# bln-002.net
KiCad netlist of a schematic drawn in EAGLE
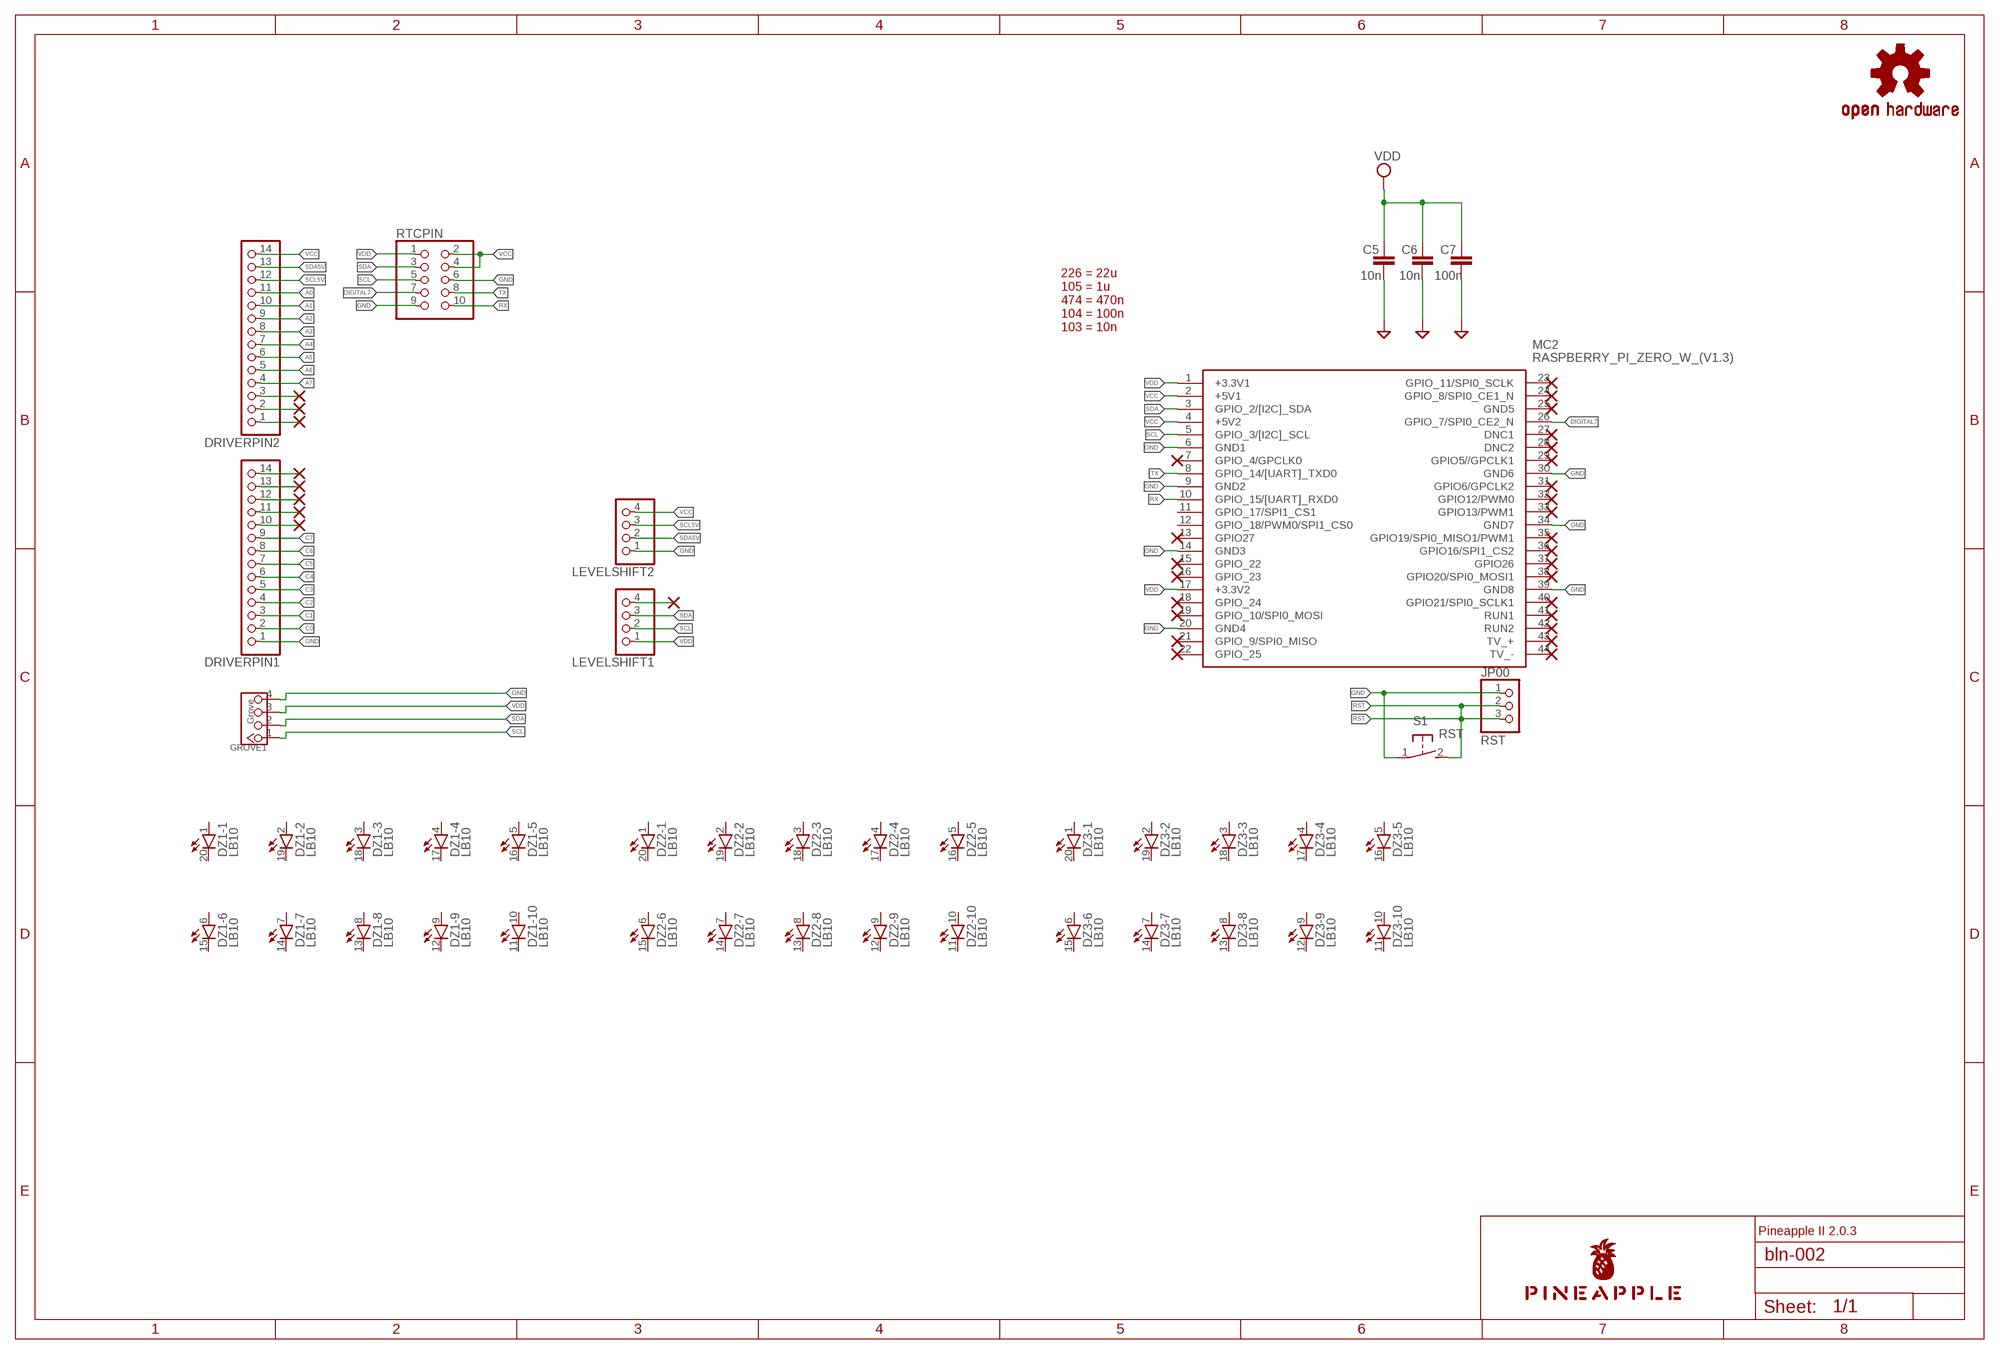
[diagram p0: schematic, sheet 1]

(export (version "E")
  (design (tool "Eeschema 10.0.6"))
  (components
    (comp (ref "C5")
      (value "10n")
      (footprint "eagle-import:C025-024X044")
      (libsource (lib "eagle-import") (part "C-EU025-024X044"))
    )
    (comp (ref "C6")
      (value "10n")
      (footprint "eagle-import:C025-024X044")
      (libsource (lib "eagle-import") (part "C-EU025-024X044"))
    )
    (comp (ref "C7")
      (value "100n")
      (footprint "eagle-import:C025-024X044")
      (libsource (lib "eagle-import") (part "C-EU025-024X044"))
    )
    (comp (ref "DRIVERPIN1")
      (value "PINHD-1X14")
      (footprint "eagle-import:1X14")
      (libsource (lib "eagle-import") (part "PINHD-1X14"))
    )
    (comp (ref "DRIVERPIN2")
      (value "PINHD-1X14")
      (footprint "eagle-import:1X14")
      (libsource (lib "eagle-import") (part "PINHD-1X14"))
    )
    (comp (ref "DZ1")
      (value "LB10")
      (footprint "eagle-import:LB10")
      (libsource (lib "eagle-import") (part "LB10"))
    )
    (comp (ref "DZ2")
      (value "LB10")
      (footprint "eagle-import:LB10")
      (libsource (lib "eagle-import") (part "LB10"))
    )
    (comp (ref "DZ3")
      (value "LB10")
      (footprint "eagle-import:LB10")
      (libsource (lib "eagle-import") (part "LB10"))
    )
    (comp (ref "GROVE1")
      (value "Grove")
      (footprint "eagle-import:4P-2.0-90D")
      (libsource (lib "eagle-import") (part "TWIG-4P-2.0'90D'"))
    )
    (comp (ref "JP00")
      (value "RST")
      (footprint "eagle-import:1X03")
      (libsource (lib "eagle-import") (part "PINHD-1X3"))
    )
    (comp (ref "LEVELSHIFT1")
      (value "PINHD-1X4")
      (footprint "eagle-import:1X04")
      (libsource (lib "eagle-import") (part "PINHD-1X4"))
    )
    (comp (ref "LEVELSHIFT2")
      (value "PINHD-1X4")
      (footprint "eagle-import:1X04")
      (libsource (lib "eagle-import") (part "PINHD-1X4"))
    )
    (comp (ref "LOGO1")
      (value "OSHW-LOGOS-COPPER")
      (footprint "eagle-import:OSHW-LOGO-S_COPPER")
      (libsource (lib "eagle-import") (part "OSHW-LOGOS-COPPER"))
    )
    (comp (ref "MC2")
      (value "RASPBERRY_PI_ZERO_W_(V1.3)")
      (footprint "eagle-import:RASPBERRYPIZEROWV13")
      (fields (field (name "ARROW_PART_NUMBER") "Raspberry Pi Zero W (v1.3)"))
      (libsource (lib "eagle-import") (part "RASPBERRY_PI_ZERO_W_(V1.3)"))
    )
    (comp (ref "RTCPIN")
      (value "PINHD-2X5")
      (footprint "eagle-import:2X05")
      (libsource (lib "eagle-import") (part "PINHD-2X5"))
    )
    (comp (ref "S1")
      (value "RST")
      (footprint "eagle-import:B3F-31XX")
      (fields (field (name "MPN") "B3F-3100"))
      (libsource (lib "eagle-import") (part "31-XX"))
    )
    (comp (ref "U$1")
      (value "PINEAPPLE450_SILK")
      (footprint "eagle-import:PINEAPPLE450_SILK")
      (libsource (lib "eagle-import") (part "PINEAPPLE450_SILK"))
    )
  )
  (nets
    (net (code "1") (name "A0") (class "Default")
      (node (ref "DRIVERPIN2") (pin "11") (pinfunction "11_11") (pintype "passive"))
    )
    (net (code "2") (name "A1") (class "Default")
      (node (ref "DRIVERPIN2") (pin "10") (pinfunction "10_10") (pintype "passive"))
    )
    (net (code "3") (name "A2") (class "Default")
      (node (ref "DRIVERPIN2") (pin "9") (pinfunction "9_9") (pintype "passive"))
    )
    (net (code "4") (name "A3") (class "Default")
      (node (ref "DRIVERPIN2") (pin "8") (pinfunction "8_8") (pintype "passive"))
    )
    (net (code "5") (name "A4") (class "Default")
      (node (ref "DRIVERPIN2") (pin "7") (pinfunction "7_7") (pintype "passive"))
    )
    (net (code "6") (name "A5") (class "Default")
      (node (ref "DRIVERPIN2") (pin "6") (pinfunction "6_6") (pintype "passive"))
    )
    (net (code "7") (name "A6") (class "Default")
      (node (ref "DRIVERPIN2") (pin "5") (pinfunction "5_5") (pintype "passive"))
    )
    (net (code "8") (name "A7") (class "Default")
      (node (ref "DRIVERPIN2") (pin "4") (pinfunction "4_4") (pintype "passive"))
    )
    (net (code "9") (name "C0") (class "Default")
      (node (ref "DRIVERPIN1") (pin "2") (pinfunction "2_2") (pintype "passive"))
    )
    (net (code "10") (name "C1") (class "Default")
      (node (ref "DRIVERPIN1") (pin "3") (pinfunction "3_3") (pintype "passive"))
    )
    (net (code "11") (name "C2") (class "Default")
      (node (ref "DRIVERPIN1") (pin "4") (pinfunction "4_4") (pintype "passive"))
    )
    (net (code "12") (name "C3") (class "Default")
      (node (ref "DRIVERPIN1") (pin "5") (pinfunction "5_5") (pintype "passive"))
    )
    (net (code "13") (name "C4") (class "Default")
      (node (ref "DRIVERPIN1") (pin "6") (pinfunction "6_6") (pintype "passive"))
    )
    (net (code "14") (name "C5") (class "Default")
      (node (ref "DRIVERPIN1") (pin "7") (pinfunction "7_7") (pintype "passive"))
    )
    (net (code "15") (name "C6") (class "Default")
      (node (ref "DRIVERPIN1") (pin "8") (pinfunction "8_8") (pintype "passive"))
    )
    (net (code "16") (name "C7") (class "Default")
      (node (ref "DRIVERPIN1") (pin "9") (pinfunction "9_9") (pintype "passive"))
    )
    (net (code "17") (name "DIGITAL7") (class "Default")
      (node (ref "MC2") (pin "26") (pinfunction "GPIO_7/SPI0_CE2_N_26") (pintype "bidirectional"))
      (node (ref "RTCPIN") (pin "7") (pinfunction "7_7") (pintype "passive"))
    )
    (net (code "18") (name "GND") (class "Default")
      (node (ref "C5") (pin "2") (pinfunction "2_2") (pintype "passive"))
      (node (ref "C6") (pin "2") (pinfunction "2_2") (pintype "passive"))
      (node (ref "C7") (pin "2") (pinfunction "2_2") (pintype "passive"))
      (node (ref "DRIVERPIN1") (pin "1") (pinfunction "1_1") (pintype "passive"))
      (node (ref "GROVE1") (pin "4") (pinfunction "4_4") (pintype "bidirectional"))
      (node (ref "JP00") (pin "1") (pinfunction "1_1") (pintype "passive"))
      (node (ref "LEVELSHIFT2") (pin "1") (pinfunction "1_1") (pintype "passive"))
      (node (ref "MC2") (pin "14") (pinfunction "GND3_14") (pintype "bidirectional"))
      (node (ref "MC2") (pin "20") (pinfunction "GND4_20") (pintype "bidirectional"))
      (node (ref "MC2") (pin "30") (pinfunction "GND6_30") (pintype "bidirectional"))
      (node (ref "MC2") (pin "34") (pinfunction "GND7_34") (pintype "bidirectional"))
      (node (ref "MC2") (pin "39") (pinfunction "GND8_39") (pintype "bidirectional"))
      (node (ref "MC2") (pin "6") (pinfunction "GND1_6") (pintype "bidirectional"))
      (node (ref "MC2") (pin "9") (pinfunction "GND2_9") (pintype "bidirectional"))
      (node (ref "RTCPIN") (pin "6") (pinfunction "6_6") (pintype "passive"))
      (node (ref "RTCPIN") (pin "9") (pinfunction "9_9") (pintype "passive"))
      (node (ref "S1") (pin "1") (pinfunction "P_1") (pintype "passive"))
    )
    (net (code "19") (name "RST") (class "Default")
      (node (ref "JP00") (pin "2") (pinfunction "2_2") (pintype "passive"))
      (node (ref "JP00") (pin "3") (pinfunction "3_3") (pintype "passive"))
      (node (ref "S1") (pin "2") (pinfunction "S_2") (pintype "passive"))
    )
    (net (code "20") (name "RX") (class "Default")
      (node (ref "MC2") (pin "10") (pinfunction "GPIO_15/[UART]_RXD0_10") (pintype "bidirectional"))
      (node (ref "RTCPIN") (pin "10") (pinfunction "10_10") (pintype "passive"))
    )
    (net (code "21") (name "SCL") (class "Default")
      (node (ref "GROVE1") (pin "1") (pinfunction "1_1") (pintype "bidirectional"))
      (node (ref "LEVELSHIFT1") (pin "2") (pinfunction "2_2") (pintype "passive"))
      (node (ref "MC2") (pin "5") (pinfunction "GPIO_3/[I2C]_SCL_5") (pintype "bidirectional"))
      (node (ref "RTCPIN") (pin "5") (pinfunction "5_5") (pintype "passive"))
    )
    (net (code "22") (name "SCL5V") (class "Default")
      (node (ref "DRIVERPIN2") (pin "12") (pinfunction "12_12") (pintype "passive"))
      (node (ref "LEVELSHIFT2") (pin "3") (pinfunction "3_3") (pintype "passive"))
    )
    (net (code "23") (name "SDA") (class "Default")
      (node (ref "GROVE1") (pin "2") (pinfunction "2_2") (pintype "bidirectional"))
      (node (ref "LEVELSHIFT1") (pin "3") (pinfunction "3_3") (pintype "passive"))
      (node (ref "MC2") (pin "3") (pinfunction "GPIO_2/[I2C]_SDA_3") (pintype "bidirectional"))
      (node (ref "RTCPIN") (pin "3") (pinfunction "3_3") (pintype "passive"))
    )
    (net (code "24") (name "SDA5V") (class "Default")
      (node (ref "DRIVERPIN2") (pin "13") (pinfunction "13_13") (pintype "passive"))
      (node (ref "LEVELSHIFT2") (pin "2") (pinfunction "2_2") (pintype "passive"))
    )
    (net (code "25") (name "TX") (class "Default")
      (node (ref "MC2") (pin "8") (pinfunction "GPIO_14/[UART]_TXD0_8") (pintype "bidirectional"))
      (node (ref "RTCPIN") (pin "8") (pinfunction "8_8") (pintype "passive"))
    )
    (net (code "26") (name "VCC") (class "Default")
      (node (ref "DRIVERPIN2") (pin "14") (pinfunction "14_14") (pintype "passive"))
      (node (ref "LEVELSHIFT2") (pin "4") (pinfunction "4_4") (pintype "passive"))
      (node (ref "MC2") (pin "2") (pinfunction "+5V1_2") (pintype "bidirectional"))
      (node (ref "MC2") (pin "4") (pinfunction "+5V2_4") (pintype "bidirectional"))
      (node (ref "RTCPIN") (pin "2") (pinfunction "2_2") (pintype "passive"))
      (node (ref "RTCPIN") (pin "4") (pinfunction "4_4") (pintype "passive"))
    )
    (net (code "27") (name "VDD") (class "Default")
      (node (ref "C5") (pin "1") (pinfunction "1_1") (pintype "passive"))
      (node (ref "C6") (pin "1") (pinfunction "1_1") (pintype "passive"))
      (node (ref "C7") (pin "1") (pinfunction "1_1") (pintype "passive"))
      (node (ref "GROVE1") (pin "3") (pinfunction "3_3") (pintype "bidirectional"))
      (node (ref "LEVELSHIFT1") (pin "1") (pinfunction "1_1") (pintype "passive"))
      (node (ref "MC2") (pin "1") (pinfunction "+3.3V1_1") (pintype "bidirectional"))
      (node (ref "MC2") (pin "17") (pinfunction "+3.3V2_17") (pintype "bidirectional"))
      (node (ref "RTCPIN") (pin "1") (pinfunction "1_1") (pintype "passive"))
    )
    (net (code "28") (name "unconnected-(DRIVERPIN1-Pad10)") (class "Default")
      (node (ref "DRIVERPIN1") (pin "10") (pinfunction "10_10") (pintype "passive"))
    )
    (net (code "29") (name "unconnected-(DRIVERPIN1-Pad11)") (class "Default")
      (node (ref "DRIVERPIN1") (pin "11") (pinfunction "11_11") (pintype "passive"))
    )
    (net (code "30") (name "unconnected-(DRIVERPIN1-Pad12)") (class "Default")
      (node (ref "DRIVERPIN1") (pin "12") (pinfunction "12_12") (pintype "passive"))
    )
    (net (code "31") (name "unconnected-(DRIVERPIN1-Pad13)") (class "Default")
      (node (ref "DRIVERPIN1") (pin "13") (pinfunction "13_13") (pintype "passive"))
    )
    (net (code "32") (name "unconnected-(DRIVERPIN1-Pad14)") (class "Default")
      (node (ref "DRIVERPIN1") (pin "14") (pinfunction "14_14") (pintype "passive"))
    )
    (net (code "33") (name "unconnected-(DRIVERPIN2-Pad1)") (class "Default")
      (node (ref "DRIVERPIN2") (pin "1") (pinfunction "1_1") (pintype "passive"))
    )
    (net (code "34") (name "unconnected-(DRIVERPIN2-Pad2)") (class "Default")
      (node (ref "DRIVERPIN2") (pin "2") (pinfunction "2_2") (pintype "passive"))
    )
    (net (code "35") (name "unconnected-(DRIVERPIN2-Pad3)") (class "Default")
      (node (ref "DRIVERPIN2") (pin "3") (pinfunction "3_3") (pintype "passive"))
    )
    (net (code "36") (name "unconnected-(DZ1A-A-Pad1)") (class "Default")
      (node (ref "DZ1") (pin "1") (pinfunction "A_1") (pintype "passive"))
    )
    (net (code "37") (name "unconnected-(DZ1A-C-Pad20)") (class "Default")
      (node (ref "DZ1") (pin "20") (pinfunction "C_20") (pintype "passive"))
    )
    (net (code "38") (name "unconnected-(DZ1B-A-Pad10)") (class "Default")
      (node (ref "DZ1") (pin "10") (pinfunction "A_10") (pintype "passive"))
    )
    (net (code "39") (name "unconnected-(DZ1B-C-Pad11)") (class "Default")
      (node (ref "DZ1") (pin "11") (pinfunction "C_11") (pintype "passive"))
    )
    (net (code "40") (name "unconnected-(DZ1C-A-Pad2)") (class "Default")
      (node (ref "DZ1") (pin "2") (pinfunction "A_2") (pintype "passive"))
    )
    (net (code "41") (name "unconnected-(DZ1C-C-Pad19)") (class "Default")
      (node (ref "DZ1") (pin "19") (pinfunction "C_19") (pintype "passive"))
    )
    (net (code "42") (name "unconnected-(DZ1D-A-Pad3)") (class "Default")
      (node (ref "DZ1") (pin "3") (pinfunction "A_3") (pintype "passive"))
    )
    (net (code "43") (name "unconnected-(DZ1D-C-Pad18)") (class "Default")
      (node (ref "DZ1") (pin "18") (pinfunction "C_18") (pintype "passive"))
    )
    (net (code "44") (name "unconnected-(DZ1E-A-Pad4)") (class "Default")
      (node (ref "DZ1") (pin "4") (pinfunction "A_4") (pintype "passive"))
    )
    (net (code "45") (name "unconnected-(DZ1E-C-Pad17)") (class "Default")
      (node (ref "DZ1") (pin "17") (pinfunction "C_17") (pintype "passive"))
    )
    (net (code "46") (name "unconnected-(DZ1F-A-Pad5)") (class "Default")
      (node (ref "DZ1") (pin "5") (pinfunction "A_5") (pintype "passive"))
    )
    (net (code "47") (name "unconnected-(DZ1F-C-Pad16)") (class "Default")
      (node (ref "DZ1") (pin "16") (pinfunction "C_16") (pintype "passive"))
    )
    (net (code "48") (name "unconnected-(DZ1G-A-Pad6)") (class "Default")
      (node (ref "DZ1") (pin "6") (pinfunction "A_6") (pintype "passive"))
    )
    (net (code "49") (name "unconnected-(DZ1G-C-Pad15)") (class "Default")
      (node (ref "DZ1") (pin "15") (pinfunction "C_15") (pintype "passive"))
    )
    (net (code "50") (name "unconnected-(DZ1H-A-Pad7)") (class "Default")
      (node (ref "DZ1") (pin "7") (pinfunction "A_7") (pintype "passive"))
    )
    (net (code "51") (name "unconnected-(DZ1H-C-Pad14)") (class "Default")
      (node (ref "DZ1") (pin "14") (pinfunction "C_14") (pintype "passive"))
    )
    (net (code "52") (name "unconnected-(DZ1I-A-Pad8)") (class "Default")
      (node (ref "DZ1") (pin "8") (pinfunction "A_8") (pintype "passive"))
    )
    (net (code "53") (name "unconnected-(DZ1I-C-Pad13)") (class "Default")
      (node (ref "DZ1") (pin "13") (pinfunction "C_13") (pintype "passive"))
    )
    (net (code "54") (name "unconnected-(DZ1J-A-Pad9)") (class "Default")
      (node (ref "DZ1") (pin "9") (pinfunction "A_9") (pintype "passive"))
    )
    (net (code "55") (name "unconnected-(DZ1J-C-Pad12)") (class "Default")
      (node (ref "DZ1") (pin "12") (pinfunction "C_12") (pintype "passive"))
    )
    (net (code "56") (name "unconnected-(DZ2A-A-Pad1)") (class "Default")
      (node (ref "DZ2") (pin "1") (pinfunction "A_1") (pintype "passive"))
    )
    (net (code "57") (name "unconnected-(DZ2A-C-Pad20)") (class "Default")
      (node (ref "DZ2") (pin "20") (pinfunction "C_20") (pintype "passive"))
    )
    (net (code "58") (name "unconnected-(DZ2B-A-Pad10)") (class "Default")
      (node (ref "DZ2") (pin "10") (pinfunction "A_10") (pintype "passive"))
    )
    (net (code "59") (name "unconnected-(DZ2B-C-Pad11)") (class "Default")
      (node (ref "DZ2") (pin "11") (pinfunction "C_11") (pintype "passive"))
    )
    (net (code "60") (name "unconnected-(DZ2C-A-Pad2)") (class "Default")
      (node (ref "DZ2") (pin "2") (pinfunction "A_2") (pintype "passive"))
    )
    (net (code "61") (name "unconnected-(DZ2C-C-Pad19)") (class "Default")
      (node (ref "DZ2") (pin "19") (pinfunction "C_19") (pintype "passive"))
    )
    (net (code "62") (name "unconnected-(DZ2D-A-Pad3)") (class "Default")
      (node (ref "DZ2") (pin "3") (pinfunction "A_3") (pintype "passive"))
    )
    (net (code "63") (name "unconnected-(DZ2D-C-Pad18)") (class "Default")
      (node (ref "DZ2") (pin "18") (pinfunction "C_18") (pintype "passive"))
    )
    (net (code "64") (name "unconnected-(DZ2E-A-Pad4)") (class "Default")
      (node (ref "DZ2") (pin "4") (pinfunction "A_4") (pintype "passive"))
    )
    (net (code "65") (name "unconnected-(DZ2E-C-Pad17)") (class "Default")
      (node (ref "DZ2") (pin "17") (pinfunction "C_17") (pintype "passive"))
    )
    (net (code "66") (name "unconnected-(DZ2F-A-Pad5)") (class "Default")
      (node (ref "DZ2") (pin "5") (pinfunction "A_5") (pintype "passive"))
    )
    (net (code "67") (name "unconnected-(DZ2F-C-Pad16)") (class "Default")
      (node (ref "DZ2") (pin "16") (pinfunction "C_16") (pintype "passive"))
    )
    (net (code "68") (name "unconnected-(DZ2G-A-Pad6)") (class "Default")
      (node (ref "DZ2") (pin "6") (pinfunction "A_6") (pintype "passive"))
    )
    (net (code "69") (name "unconnected-(DZ2G-C-Pad15)") (class "Default")
      (node (ref "DZ2") (pin "15") (pinfunction "C_15") (pintype "passive"))
    )
    (net (code "70") (name "unconnected-(DZ2H-A-Pad7)") (class "Default")
      (node (ref "DZ2") (pin "7") (pinfunction "A_7") (pintype "passive"))
    )
    (net (code "71") (name "unconnected-(DZ2H-C-Pad14)") (class "Default")
      (node (ref "DZ2") (pin "14") (pinfunction "C_14") (pintype "passive"))
    )
    (net (code "72") (name "unconnected-(DZ2I-A-Pad8)") (class "Default")
      (node (ref "DZ2") (pin "8") (pinfunction "A_8") (pintype "passive"))
    )
    (net (code "73") (name "unconnected-(DZ2I-C-Pad13)") (class "Default")
      (node (ref "DZ2") (pin "13") (pinfunction "C_13") (pintype "passive"))
    )
    (net (code "74") (name "unconnected-(DZ2J-A-Pad9)") (class "Default")
      (node (ref "DZ2") (pin "9") (pinfunction "A_9") (pintype "passive"))
    )
    (net (code "75") (name "unconnected-(DZ2J-C-Pad12)") (class "Default")
      (node (ref "DZ2") (pin "12") (pinfunction "C_12") (pintype "passive"))
    )
    (net (code "76") (name "unconnected-(DZ3A-A-Pad1)") (class "Default")
      (node (ref "DZ3") (pin "1") (pinfunction "A_1") (pintype "passive"))
    )
    (net (code "77") (name "unconnected-(DZ3A-C-Pad20)") (class "Default")
      (node (ref "DZ3") (pin "20") (pinfunction "C_20") (pintype "passive"))
    )
    (net (code "78") (name "unconnected-(DZ3B-A-Pad10)") (class "Default")
      (node (ref "DZ3") (pin "10") (pinfunction "A_10") (pintype "passive"))
    )
    (net (code "79") (name "unconnected-(DZ3B-C-Pad11)") (class "Default")
      (node (ref "DZ3") (pin "11") (pinfunction "C_11") (pintype "passive"))
    )
    (net (code "80") (name "unconnected-(DZ3C-A-Pad2)") (class "Default")
      (node (ref "DZ3") (pin "2") (pinfunction "A_2") (pintype "passive"))
    )
    (net (code "81") (name "unconnected-(DZ3C-C-Pad19)") (class "Default")
      (node (ref "DZ3") (pin "19") (pinfunction "C_19") (pintype "passive"))
    )
    (net (code "82") (name "unconnected-(DZ3D-A-Pad3)") (class "Default")
      (node (ref "DZ3") (pin "3") (pinfunction "A_3") (pintype "passive"))
    )
    (net (code "83") (name "unconnected-(DZ3D-C-Pad18)") (class "Default")
      (node (ref "DZ3") (pin "18") (pinfunction "C_18") (pintype "passive"))
    )
    (net (code "84") (name "unconnected-(DZ3E-A-Pad4)") (class "Default")
      (node (ref "DZ3") (pin "4") (pinfunction "A_4") (pintype "passive"))
    )
    (net (code "85") (name "unconnected-(DZ3E-C-Pad17)") (class "Default")
      (node (ref "DZ3") (pin "17") (pinfunction "C_17") (pintype "passive"))
    )
    (net (code "86") (name "unconnected-(DZ3F-A-Pad5)") (class "Default")
      (node (ref "DZ3") (pin "5") (pinfunction "A_5") (pintype "passive"))
    )
    (net (code "87") (name "unconnected-(DZ3F-C-Pad16)") (class "Default")
      (node (ref "DZ3") (pin "16") (pinfunction "C_16") (pintype "passive"))
    )
    (net (code "88") (name "unconnected-(DZ3G-A-Pad6)") (class "Default")
      (node (ref "DZ3") (pin "6") (pinfunction "A_6") (pintype "passive"))
    )
    (net (code "89") (name "unconnected-(DZ3G-C-Pad15)") (class "Default")
      (node (ref "DZ3") (pin "15") (pinfunction "C_15") (pintype "passive"))
    )
    (net (code "90") (name "unconnected-(DZ3H-A-Pad7)") (class "Default")
      (node (ref "DZ3") (pin "7") (pinfunction "A_7") (pintype "passive"))
    )
    (net (code "91") (name "unconnected-(DZ3H-C-Pad14)") (class "Default")
      (node (ref "DZ3") (pin "14") (pinfunction "C_14") (pintype "passive"))
    )
    (net (code "92") (name "unconnected-(DZ3I-A-Pad8)") (class "Default")
      (node (ref "DZ3") (pin "8") (pinfunction "A_8") (pintype "passive"))
    )
    (net (code "93") (name "unconnected-(DZ3I-C-Pad13)") (class "Default")
      (node (ref "DZ3") (pin "13") (pinfunction "C_13") (pintype "passive"))
    )
    (net (code "94") (name "unconnected-(DZ3J-A-Pad9)") (class "Default")
      (node (ref "DZ3") (pin "9") (pinfunction "A_9") (pintype "passive"))
    )
    (net (code "95") (name "unconnected-(DZ3J-C-Pad12)") (class "Default")
      (node (ref "DZ3") (pin "12") (pinfunction "C_12") (pintype "passive"))
    )
    (net (code "96") (name "unconnected-(LEVELSHIFT1-Pad4)") (class "Default")
      (node (ref "LEVELSHIFT1") (pin "4") (pinfunction "4_4") (pintype "passive"))
    )
    (net (code "97") (name "unconnected-(MC2-DNC1-Pad27)") (class "Default")
      (node (ref "MC2") (pin "27") (pinfunction "DNC1_27") (pintype "bidirectional"))
    )
    (net (code "98") (name "unconnected-(MC2-DNC2-Pad28)") (class "Default")
      (node (ref "MC2") (pin "28") (pinfunction "DNC2_28") (pintype "bidirectional"))
    )
    (net (code "99") (name "unconnected-(MC2-GND5-Pad25)") (class "Default")
      (node (ref "MC2") (pin "25") (pinfunction "GND5_25") (pintype "bidirectional"))
    )
    (net (code "100") (name "unconnected-(MC2-GPIO5{slash}{slash}GPCLK1-Pad29)") (class "Default")
      (node (ref "MC2") (pin "29") (pinfunction "GPIO5//GPCLK1_29") (pintype "bidirectional"))
    )
    (net (code "101") (name "unconnected-(MC2-GPIO6{slash}GPCLK2-Pad31)") (class "Default")
      (node (ref "MC2") (pin "31") (pinfunction "GPIO6/GPCLK2_31") (pintype "bidirectional"))
    )
    (net (code "102") (name "unconnected-(MC2-GPIO12{slash}PWM0-Pad32)") (class "Default")
      (node (ref "MC2") (pin "32") (pinfunction "GPIO12/PWM0_32") (pintype "bidirectional"))
    )
    (net (code "103") (name "unconnected-(MC2-GPIO13{slash}PWM1-Pad33)") (class "Default")
      (node (ref "MC2") (pin "33") (pinfunction "GPIO13/PWM1_33") (pintype "bidirectional"))
    )
    (net (code "104") (name "unconnected-(MC2-GPIO16{slash}SPI1_CS2-Pad36)") (class "Default")
      (node (ref "MC2") (pin "36") (pinfunction "GPIO16/SPI1_CS2_36") (pintype "bidirectional"))
    )
    (net (code "105") (name "unconnected-(MC2-GPIO19{slash}SPI0_MISO1{slash}PWM1-Pad35)") (class "Default")
      (node (ref "MC2") (pin "35") (pinfunction "GPIO19/SPI0_MISO1/PWM1_35") (pintype "bidirectional"))
    )
    (net (code "106") (name "unconnected-(MC2-GPIO20{slash}SPI0_MOSI1-Pad38)") (class "Default")
      (node (ref "MC2") (pin "38") (pinfunction "GPIO20/SPI0_MOSI1_38") (pintype "bidirectional"))
    )
    (net (code "107") (name "unconnected-(MC2-GPIO21{slash}SPI0_SCLK1-Pad40)") (class "Default")
      (node (ref "MC2") (pin "40") (pinfunction "GPIO21/SPI0_SCLK1_40") (pintype "bidirectional"))
    )
    (net (code "108") (name "unconnected-(MC2-GPIO26-Pad37)") (class "Default")
      (node (ref "MC2") (pin "37") (pinfunction "GPIO26_37") (pintype "bidirectional"))
    )
    (net (code "109") (name "unconnected-(MC2-GPIO27-Pad13)") (class "Default")
      (node (ref "MC2") (pin "13") (pinfunction "GPIO27_13") (pintype "bidirectional"))
    )
    (net (code "110") (name "unconnected-(MC2-GPIO_4{slash}GPCLK0-Pad7)") (class "Default")
      (node (ref "MC2") (pin "7") (pinfunction "GPIO_4/GPCLK0_7") (pintype "bidirectional"))
    )
    (net (code "111") (name "unconnected-(MC2-GPIO_8{slash}SPI0_CE1_N-Pad24)") (class "Default")
      (node (ref "MC2") (pin "24") (pinfunction "GPIO_8/SPI0_CE1_N_24") (pintype "bidirectional"))
    )
    (net (code "112") (name "unconnected-(MC2-GPIO_9{slash}SPI0_MISO-Pad21)") (class "Default")
      (node (ref "MC2") (pin "21") (pinfunction "GPIO_9/SPI0_MISO_21") (pintype "bidirectional"))
    )
    (net (code "113") (name "unconnected-(MC2-GPIO_10{slash}SPI0_MOSI-Pad19)") (class "Default")
      (node (ref "MC2") (pin "19") (pinfunction "GPIO_10/SPI0_MOSI_19") (pintype "bidirectional"))
    )
    (net (code "114") (name "unconnected-(MC2-GPIO_11{slash}SPI0_SCLK-Pad23)") (class "Default")
      (node (ref "MC2") (pin "23") (pinfunction "GPIO_11/SPI0_SCLK_23") (pintype "bidirectional"))
    )
    (net (code "115") (name "unconnected-(MC2-GPIO_17{slash}SPI1_CS1-Pad11)") (class "Default")
      (node (ref "MC2") (pin "11") (pinfunction "GPIO_17/SPI1_CS1_11") (pintype "bidirectional"))
    )
    (net (code "116") (name "unconnected-(MC2-GPIO_18{slash}PWM0{slash}SPI1_CS0-Pad12)") (class "Default")
      (node (ref "MC2") (pin "12") (pinfunction "GPIO_18/PWM0/SPI1_CS0_12") (pintype "bidirectional"))
    )
    (net (code "117") (name "unconnected-(MC2-GPIO_22-Pad15)") (class "Default")
      (node (ref "MC2") (pin "15") (pinfunction "GPIO_22_15") (pintype "bidirectional"))
    )
    (net (code "118") (name "unconnected-(MC2-GPIO_23-Pad16)") (class "Default")
      (node (ref "MC2") (pin "16") (pinfunction "GPIO_23_16") (pintype "bidirectional"))
    )
    (net (code "119") (name "unconnected-(MC2-GPIO_24-Pad18)") (class "Default")
      (node (ref "MC2") (pin "18") (pinfunction "GPIO_24_18") (pintype "bidirectional"))
    )
    (net (code "120") (name "unconnected-(MC2-GPIO_25-Pad22)") (class "Default")
      (node (ref "MC2") (pin "22") (pinfunction "GPIO_25_22") (pintype "bidirectional"))
    )
    (net (code "121") (name "unconnected-(MC2-RUN1-Pad41)") (class "Default")
      (node (ref "MC2") (pin "41") (pinfunction "RUN1_41") (pintype "bidirectional"))
    )
    (net (code "122") (name "unconnected-(MC2-RUN2-Pad42)") (class "Default")
      (node (ref "MC2") (pin "42") (pinfunction "RUN2_42") (pintype "bidirectional"))
    )
    (net (code "123") (name "unconnected-(MC2-TV_+-Pad43)") (class "Default")
      (node (ref "MC2") (pin "43") (pinfunction "TV_+_43") (pintype "bidirectional"))
    )
    (net (code "124") (name "unconnected-(MC2-TV_--Pad44)") (class "Default")
      (node (ref "MC2") (pin "44") (pinfunction "TV_-_44") (pintype "bidirectional"))
    )
  )
)
